# joint_board_boosterpack.net
KiCad netlist of a schematic drawn in Altium Designer
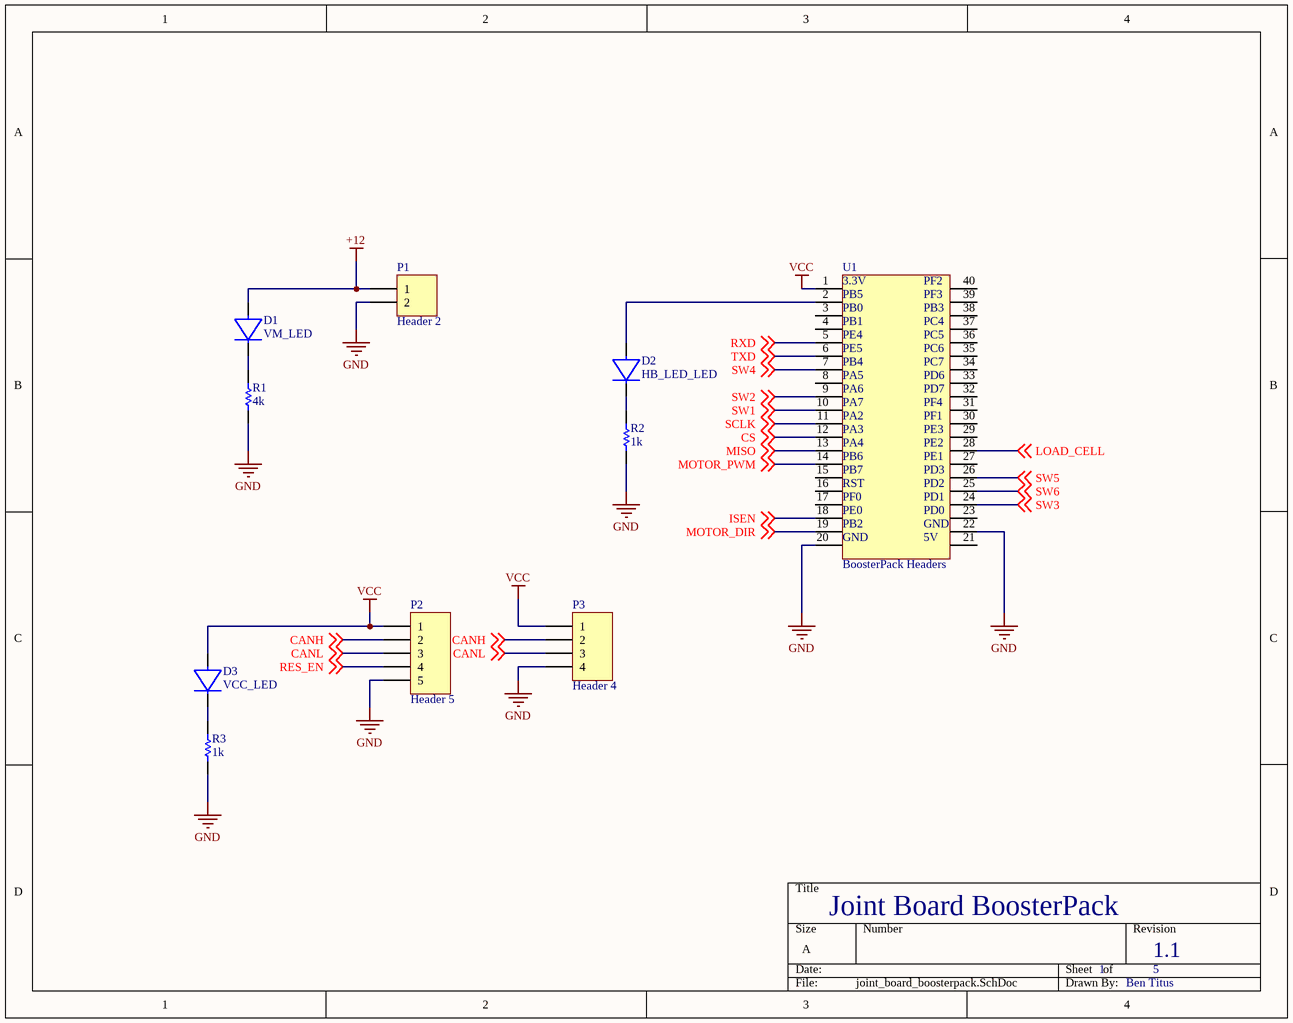
[diagram p0: joint_board_boosterpack.SchDoc]

(export (version "E")
  (design (tool "Eeschema 10.0.6"))
  (components
    (comp (ref "D1")
      (value "VM_LED")
      (footprint "0805 Diode")
      (libsource (lib "Custom_Lib") (part "SMD_LED"))
    )
    (comp (ref "D2")
      (value "HB_LED_LED")
      (footprint "0805 Diode")
      (libsource (lib "Custom_Lib") (part "SMD_LED"))
    )
    (comp (ref "D3")
      (value "VCC_LED")
      (footprint "0805 Diode")
      (libsource (lib "Custom_Lib") (part "SMD_LED"))
    )
    (comp (ref "P1")
      (value "Header 2")
      (footprint "HDR1X2")
      (description "Header, 2-Pin")
      (fields (field (name "PUBLISHER") "Altium Limited"))
      (libsource (lib "Miscellaneous Connectors") (part "Header 2"))
    )
    (comp (ref "P2")
      (value "Header 5")
      (footprint "HDR1X5")
      (description "Header, 5-Pin")
      (fields (field (name "PUBLISHER") "Altium Limited"))
      (libsource (lib "Miscellaneous Connectors") (part "Header 5"))
    )
    (comp (ref "P3")
      (value "Header 4")
      (footprint "HDR1X4")
      (description "Header, 4-Pin")
      (fields (field (name "PUBLISHER") "Altium Limited"))
      (libsource (lib "Miscellaneous Connectors") (part "Header 4"))
    )
    (comp (ref "R1")
      (value "4k")
      (footprint "RESC0805(2012)_L")
      (description "0805 (2012 Metric) Chip Resistor")
      (libsource (lib "Altium Content Vault") (part "RES_3"))
    )
    (comp (ref "R2")
      (value "1k")
      (footprint "RESC0805(2012)_L")
      (description "0805 (2012 Metric) Chip Resistor")
      (libsource (lib "Altium Content Vault") (part "RES_3"))
    )
    (comp (ref "R3")
      (value "1k")
      (footprint "RESC0805(2012)_L")
      (description "0805 (2012 Metric) Chip Resistor")
      (libsource (lib "Altium Content Vault") (part "RES_3"))
    )
    (comp (ref "U1")
      (value "BoosterPack Headers")
      (footprint "boosterpack_headers")
      (libsource (lib "boosterpack_pins") (part "BoosterPack Headers"))
    )
  )
  (nets
    (net (code "1") (name "+12") (class "Default")
      (node (ref "D1") (pin "1") (pintype "passive"))
      (node (ref "P1") (pin "1") (pinfunction "1_1") (pintype "passive"))
    )
    (net (code "2") (name "CANH") (class "Default")
      (node (ref "P2") (pin "2") (pinfunction "2_2") (pintype "passive"))
      (node (ref "P3") (pin "2") (pinfunction "2_2") (pintype "passive"))
    )
    (net (code "3") (name "CANL") (class "Default")
      (node (ref "P2") (pin "3") (pinfunction "3_3") (pintype "passive"))
      (node (ref "P3") (pin "3") (pinfunction "3_3") (pintype "passive"))
    )
    (net (code "4") (name "CS") (class "Default") (node (ref "U1") (pin "12") (pintype "passive")))
    (net (code "5") (name "GND") (class "Default")
      (node (ref "P1") (pin "2") (pinfunction "2_2") (pintype "passive"))
      (node (ref "P2") (pin "5") (pinfunction "5_5") (pintype "passive"))
      (node (ref "P3") (pin "4") (pinfunction "4_4") (pintype "passive"))
      (node (ref "R1") (pin "1") (pinfunction "1_1") (pintype "passive"))
      (node (ref "R2") (pin "1") (pinfunction "1_1") (pintype "passive"))
      (node (ref "R3") (pin "1") (pinfunction "1_1") (pintype "passive"))
      (node (ref "U1") (pin "20") (pintype "passive"))
      (node (ref "U1") (pin "22") (pintype "passive"))
    )
    (net (code "6") (name "ISEN") (class "Default") (node (ref "U1") (pin "18") (pintype "passive")))
    (net (code "7") (name "LOAD_CELL") (class "Default") (node (ref "U1") (pin "28") (pintype "passive")))
    (net (code "8") (name "MISO") (class "Default") (node (ref "U1") (pin "13") (pintype "passive")))
    (net (code "9") (name "MOTOR_DIR") (class "Default") (node (ref "U1") (pin "19") (pintype "passive")))
    (net (code "10") (name "MOTOR_PWM") (class "Default") (node (ref "U1") (pin "14") (pintype "passive")))
    (net (code "11") (name "Net-(D1-Pad2)") (class "Default")
      (node (ref "D1") (pin "2") (pintype "passive"))
      (node (ref "R1") (pin "2") (pinfunction "2_2") (pintype "passive"))
    )
    (net (code "12") (name "Net-(D2-Pad1)") (class "Default")
      (node (ref "D2") (pin "1") (pintype "passive"))
      (node (ref "U1") (pin "2") (pintype "passive"))
    )
    (net (code "13") (name "Net-(D2-Pad2)") (class "Default")
      (node (ref "D2") (pin "2") (pintype "passive"))
      (node (ref "R2") (pin "2") (pinfunction "2_2") (pintype "passive"))
    )
    (net (code "14") (name "Net-(D3-Pad2)") (class "Default")
      (node (ref "D3") (pin "2") (pintype "passive"))
      (node (ref "R3") (pin "2") (pinfunction "2_2") (pintype "passive"))
    )
    (net (code "15") (name "RES_EN") (class "Default")
      (node (ref "P2") (pin "4") (pinfunction "4_4") (pintype "passive"))
    )
    (net (code "16") (name "RXD") (class "Default") (node (ref "U1") (pin "5") (pintype "passive")))
    (net (code "17") (name "SCLK") (class "Default") (node (ref "U1") (pin "11") (pintype "passive")))
    (net (code "18") (name "SW1") (class "Default") (node (ref "U1") (pin "10") (pintype "passive")))
    (net (code "19") (name "SW2") (class "Default") (node (ref "U1") (pin "9") (pintype "passive")))
    (net (code "20") (name "SW3") (class "Default") (node (ref "U1") (pin "24") (pintype "passive")))
    (net (code "21") (name "SW4") (class "Default") (node (ref "U1") (pin "7") (pintype "passive")))
    (net (code "22") (name "SW5") (class "Default") (node (ref "U1") (pin "26") (pintype "passive")))
    (net (code "23") (name "SW6") (class "Default") (node (ref "U1") (pin "25") (pintype "passive")))
    (net (code "24") (name "TXD") (class "Default") (node (ref "U1") (pin "6") (pintype "passive")))
    (net (code "25") (name "VCC") (class "Default")
      (node (ref "D3") (pin "1") (pintype "passive"))
      (node (ref "P2") (pin "1") (pinfunction "1_1") (pintype "passive"))
      (node (ref "P3") (pin "1") (pinfunction "1_1") (pintype "passive"))
      (node (ref "U1") (pin "1") (pintype "passive"))
    )
    (net (code "26") (name "unconnected-(U1-Pad3)") (class "Default")
      (node (ref "U1") (pin "3") (pintype "passive"))
    )
    (net (code "27") (name "unconnected-(U1-Pad4)") (class "Default")
      (node (ref "U1") (pin "4") (pintype "passive"))
    )
    (net (code "28") (name "unconnected-(U1-Pad8)") (class "Default")
      (node (ref "U1") (pin "8") (pintype "passive"))
    )
    (net (code "29") (name "unconnected-(U1-Pad15)") (class "Default")
      (node (ref "U1") (pin "15") (pintype "passive"))
    )
    (net (code "30") (name "unconnected-(U1-Pad16)") (class "Default")
      (node (ref "U1") (pin "16") (pintype "passive"))
    )
    (net (code "31") (name "unconnected-(U1-Pad17)") (class "Default")
      (node (ref "U1") (pin "17") (pintype "passive"))
    )
    (net (code "32") (name "unconnected-(U1-Pad21)") (class "Default")
      (node (ref "U1") (pin "21") (pintype "passive"))
    )
    (net (code "33") (name "unconnected-(U1-Pad23)") (class "Default")
      (node (ref "U1") (pin "23") (pintype "passive"))
    )
    (net (code "34") (name "unconnected-(U1-Pad27)") (class "Default")
      (node (ref "U1") (pin "27") (pintype "passive"))
    )
    (net (code "35") (name "unconnected-(U1-Pad29)") (class "Default")
      (node (ref "U1") (pin "29") (pintype "passive"))
    )
    (net (code "36") (name "unconnected-(U1-Pad30)") (class "Default")
      (node (ref "U1") (pin "30") (pintype "passive"))
    )
    (net (code "37") (name "unconnected-(U1-Pad31)") (class "Default")
      (node (ref "U1") (pin "31") (pintype "passive"))
    )
    (net (code "38") (name "unconnected-(U1-Pad32)") (class "Default")
      (node (ref "U1") (pin "32") (pintype "passive"))
    )
    (net (code "39") (name "unconnected-(U1-Pad33)") (class "Default")
      (node (ref "U1") (pin "33") (pintype "passive"))
    )
    (net (code "40") (name "unconnected-(U1-Pad34)") (class "Default")
      (node (ref "U1") (pin "34") (pintype "passive"))
    )
    (net (code "41") (name "unconnected-(U1-Pad35)") (class "Default")
      (node (ref "U1") (pin "35") (pintype "passive"))
    )
    (net (code "42") (name "unconnected-(U1-Pad36)") (class "Default")
      (node (ref "U1") (pin "36") (pintype "passive"))
    )
    (net (code "43") (name "unconnected-(U1-Pad37)") (class "Default")
      (node (ref "U1") (pin "37") (pintype "passive"))
    )
    (net (code "44") (name "unconnected-(U1-Pad38)") (class "Default")
      (node (ref "U1") (pin "38") (pintype "passive"))
    )
    (net (code "45") (name "unconnected-(U1-Pad39)") (class "Default")
      (node (ref "U1") (pin "39") (pintype "passive"))
    )
    (net (code "46") (name "unconnected-(U1-Pad40)") (class "Default")
      (node (ref "U1") (pin "40") (pintype "passive"))
    )
  )
)
